# H.net
KiCad netlist of a schematic drawn in EAGLE
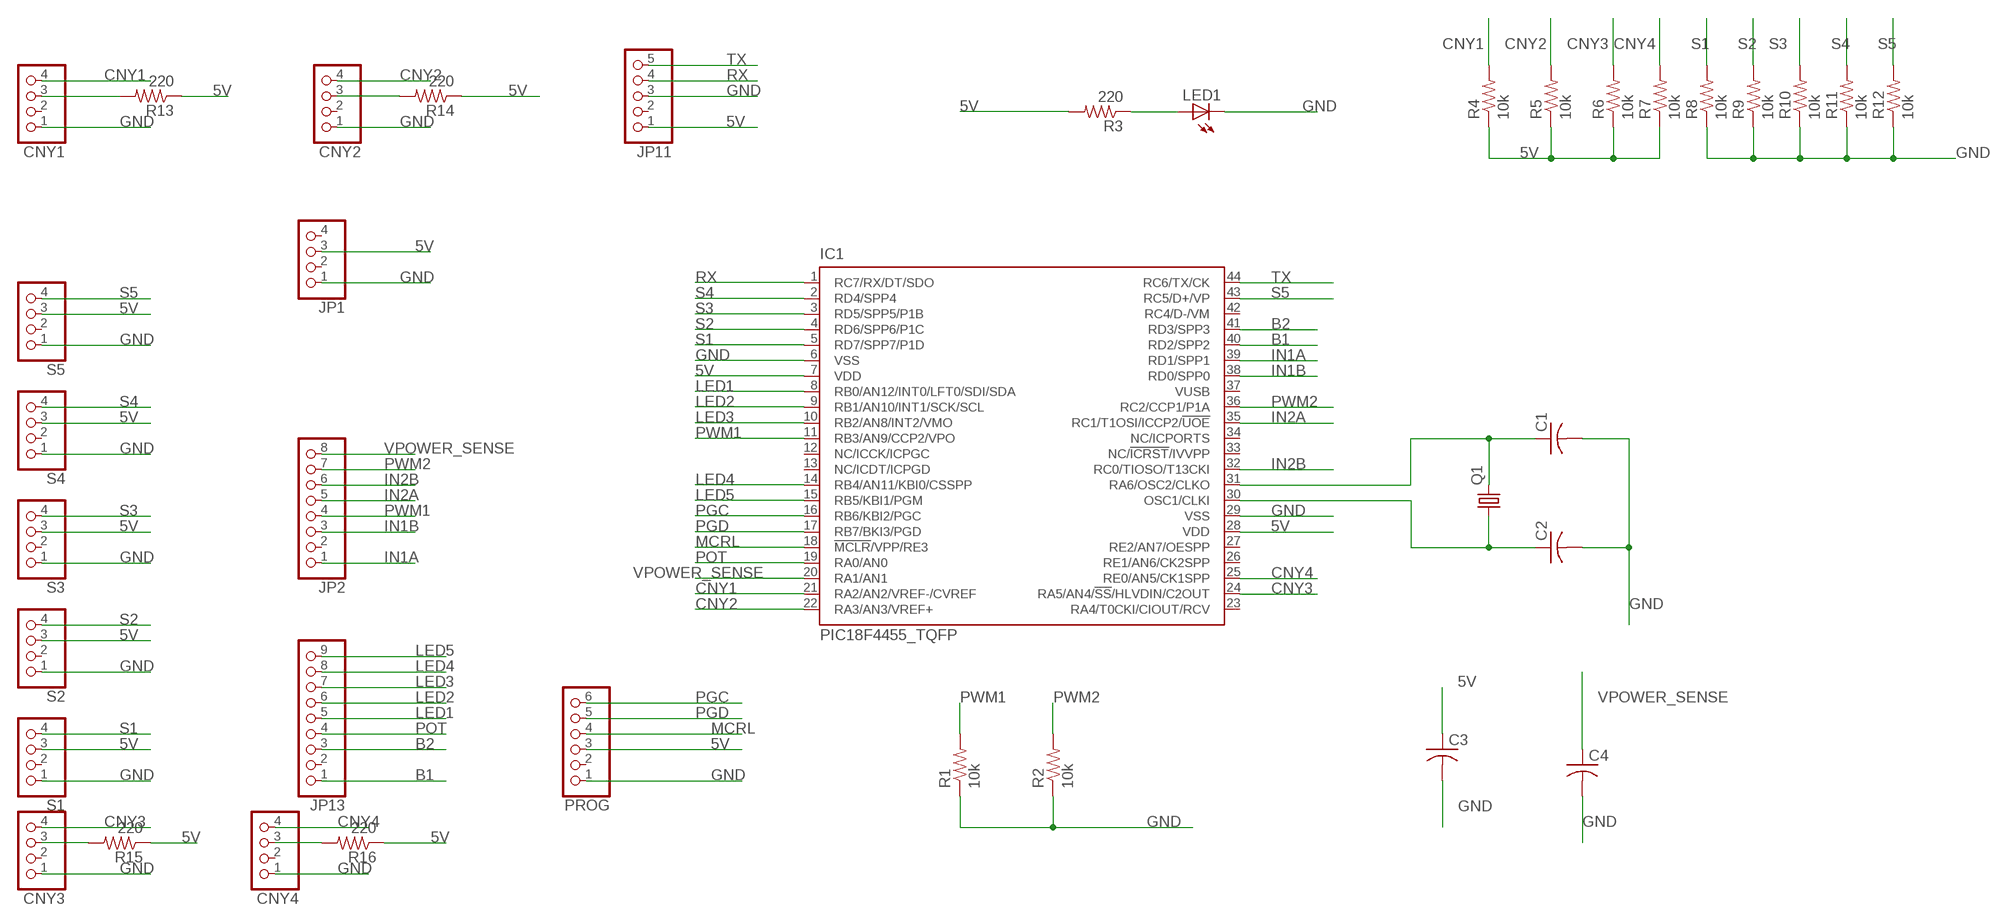
[diagram p0: schematic, sheet 1]

(export (version "E")
  (design (tool "Eeschema 10.0.6"))
  (components
    (comp (ref "C1")
      (value "C-USC0805K")
      (footprint "eagle-import:C0805K")
      (libsource (lib "eagle-import") (part "C-USC0805K"))
    )
    (comp (ref "C2")
      (value "C-USC0805K")
      (footprint "eagle-import:C0805K")
      (libsource (lib "eagle-import") (part "C-USC0805K"))
    )
    (comp (ref "C3")
      (value "C-USC0805K")
      (footprint "eagle-import:C0805K")
      (libsource (lib "eagle-import") (part "C-USC0805K"))
    )
    (comp (ref "C4")
      (value "C-USC0805K")
      (footprint "eagle-import:C0805K")
      (libsource (lib "eagle-import") (part "C-USC0805K"))
    )
    (comp (ref "CNY1")
      (value "PINHD-1X4/90")
      (footprint "eagle-import:1X04_90")
      (libsource (lib "eagle-import") (part "PINHD-1X4/90"))
    )
    (comp (ref "CNY2")
      (value "PINHD-1X4/90")
      (footprint "eagle-import:1X04_90")
      (libsource (lib "eagle-import") (part "PINHD-1X4/90"))
    )
    (comp (ref "CNY3")
      (value "PINHD-1X4/90")
      (footprint "eagle-import:1X04_90")
      (libsource (lib "eagle-import") (part "pinhead-enhanced-3_PINHD-1X4/90"))
    )
    (comp (ref "CNY4")
      (value "PINHD-1X4/90")
      (footprint "eagle-import:1X04_90")
      (libsource (lib "eagle-import") (part "pinhead-enhanced-3_PINHD-1X4/90"))
    )
    (comp (ref "IC1")
      (value "PIC18F4455_TQFP")
      (footprint "eagle-import:TQFP44")
      (fields (field (name "MF") "MICROCHIP") (field (name "MPN") "PIC18F4455-I/PT"))
      (libsource (lib "eagle-import") (part "PIC18F4_TQFP455"))
    )
    (comp (ref "JP1")
      (value "PINHD-1X4/90")
      (footprint "eagle-import:1X04_90")
      (libsource (lib "eagle-import") (part "PINHD-1X4/90"))
    )
    (comp (ref "JP2")
      (value "PINHD-1X8/90")
      (footprint "eagle-import:1X08_90")
      (libsource (lib "eagle-import") (part "PINHD-1X8/90"))
    )
    (comp (ref "JP11")
      (value "PINHD-1X5/90")
      (footprint "eagle-import:1X05_90")
      (libsource (lib "eagle-import") (part "PINHD-1X5/90"))
    )
    (comp (ref "JP13")
      (value "PINHD-1X9/90")
      (footprint "eagle-import:1X09_90")
      (libsource (lib "eagle-import") (part "PINHD-1X9/90"))
    )
    (comp (ref "LED1")
      (value "LEDCHIPLED_1206")
      (footprint "eagle-import:CHIPLED_1206")
      (libsource (lib "eagle-import") (part "LEDCHIPLED_1206"))
    )
    (comp (ref "PROG")
      (value "PINHD-1X6/90")
      (footprint "eagle-import:1X06_90")
      (libsource (lib "eagle-import") (part "PINHD-1X6/90"))
    )
    (comp (ref "Q1")
      (value "CRYSTALHC49S")
      (footprint "eagle-import:HC49_S")
      (libsource (lib "eagle-import") (part "CRYSTALHC49S"))
    )
    (comp (ref "R1")
      (value "10k")
      (footprint "eagle-import:M1206")
      (libsource (lib "eagle-import") (part "R-US_M1206"))
    )
    (comp (ref "R2")
      (value "10k")
      (footprint "eagle-import:M1206")
      (libsource (lib "eagle-import") (part "R-US_M1206"))
    )
    (comp (ref "R3")
      (value "220")
      (footprint "eagle-import:M1206")
      (libsource (lib "eagle-import") (part "R-US_M1206"))
    )
    (comp (ref "R4")
      (value "10k")
      (footprint "eagle-import:M1206")
      (libsource (lib "eagle-import") (part "R-US_M1206"))
    )
    (comp (ref "R5")
      (value "10k")
      (footprint "eagle-import:M1206")
      (libsource (lib "eagle-import") (part "R-US_M1206"))
    )
    (comp (ref "R6")
      (value "10k")
      (footprint "eagle-import:M1206")
      (libsource (lib "eagle-import") (part "R-US_M1206"))
    )
    (comp (ref "R7")
      (value "10k")
      (footprint "eagle-import:M1206")
      (libsource (lib "eagle-import") (part "R-US_M1206"))
    )
    (comp (ref "R8")
      (value "10k")
      (footprint "eagle-import:M1206")
      (libsource (lib "eagle-import") (part "R-US_M1206"))
    )
    (comp (ref "R9")
      (value "10k")
      (footprint "eagle-import:M1206")
      (libsource (lib "eagle-import") (part "R-US_M1206"))
    )
    (comp (ref "R10")
      (value "10k")
      (footprint "eagle-import:M1206")
      (libsource (lib "eagle-import") (part "R-US_M1206"))
    )
    (comp (ref "R11")
      (value "10k")
      (footprint "eagle-import:M1206")
      (libsource (lib "eagle-import") (part "R-US_M1206"))
    )
    (comp (ref "R12")
      (value "10k")
      (footprint "eagle-import:M1206")
      (libsource (lib "eagle-import") (part "R-US_M1206"))
    )
    (comp (ref "R13")
      (value "220")
      (footprint "eagle-import:M1206")
      (libsource (lib "eagle-import") (part "R-US_M1206"))
    )
    (comp (ref "R14")
      (value "220")
      (footprint "eagle-import:M1206")
      (libsource (lib "eagle-import") (part "R-US_M1206"))
    )
    (comp (ref "R15")
      (value "220")
      (footprint "eagle-import:M1206")
      (libsource (lib "eagle-import") (part "R-US_M1206"))
    )
    (comp (ref "R16")
      (value "220")
      (footprint "eagle-import:M1206")
      (libsource (lib "eagle-import") (part "R-US_M1206"))
    )
    (comp (ref "S1")
      (value "PINHD-1X4/90")
      (footprint "eagle-import:1X04_90")
      (libsource (lib "eagle-import") (part "PINHD-1X4/90"))
    )
    (comp (ref "S2")
      (value "PINHD-1X4/90")
      (footprint "eagle-import:1X04_90")
      (libsource (lib "eagle-import") (part "PINHD-1X4/90"))
    )
    (comp (ref "S3")
      (value "PINHD-1X4/90")
      (footprint "eagle-import:1X04_90")
      (libsource (lib "eagle-import") (part "PINHD-1X4/90"))
    )
    (comp (ref "S4")
      (value "PINHD-1X4/90")
      (footprint "eagle-import:1X04_90")
      (libsource (lib "eagle-import") (part "PINHD-1X4/90"))
    )
    (comp (ref "S5")
      (value "PINHD-1X4/90")
      (footprint "eagle-import:1X04_90")
      (libsource (lib "eagle-import") (part "PINHD-1X4/90"))
    )
  )
  (nets
    (net (code "1") (name "/5V") (class "Default")
      (node (ref "C3") (pin "1") (pinfunction "1_1") (pintype "passive"))
      (node (ref "IC1") (pin "28") (pinfunction "VDD_28") (pintype "power_in"))
      (node (ref "IC1") (pin "7") (pinfunction "VDD_7") (pintype "power_in"))
      (node (ref "JP1") (pin "3") (pinfunction "3_3") (pintype "passive"))
      (node (ref "JP11") (pin "1") (pinfunction "1_1") (pintype "passive"))
      (node (ref "PROG") (pin "3") (pinfunction "3_3") (pintype "passive"))
      (node (ref "R13") (pin "1") (pinfunction "1_1") (pintype "passive"))
      (node (ref "R14") (pin "1") (pinfunction "1_1") (pintype "passive"))
      (node (ref "R15") (pin "1") (pinfunction "1_1") (pintype "passive"))
      (node (ref "R16") (pin "1") (pinfunction "1_1") (pintype "passive"))
      (node (ref "R3") (pin "2") (pinfunction "2_2") (pintype "passive"))
      (node (ref "R4") (pin "1") (pinfunction "1_1") (pintype "passive"))
      (node (ref "R5") (pin "1") (pinfunction "1_1") (pintype "passive"))
      (node (ref "R6") (pin "1") (pinfunction "1_1") (pintype "passive"))
      (node (ref "R7") (pin "1") (pinfunction "1_1") (pintype "passive"))
      (node (ref "S1") (pin "3") (pinfunction "3_3") (pintype "passive"))
      (node (ref "S2") (pin "3") (pinfunction "3_3") (pintype "passive"))
      (node (ref "S3") (pin "3") (pinfunction "3_3") (pintype "passive"))
      (node (ref "S4") (pin "3") (pinfunction "3_3") (pintype "passive"))
      (node (ref "S5") (pin "3") (pinfunction "3_3") (pintype "passive"))
    )
    (net (code "2") (name "/B1") (class "Default")
      (node (ref "IC1") (pin "40") (pinfunction "RD2/SPP2_40") (pintype "bidirectional"))
      (node (ref "JP13") (pin "1") (pinfunction "1_1") (pintype "passive"))
    )
    (net (code "3") (name "/B2") (class "Default")
      (node (ref "IC1") (pin "41") (pinfunction "RD3/SPP3_41") (pintype "bidirectional"))
      (node (ref "JP13") (pin "3") (pinfunction "3_3") (pintype "passive"))
    )
    (net (code "4") (name "/CNY1") (class "Default")
      (node (ref "CNY1") (pin "4") (pinfunction "4_4") (pintype "passive"))
      (node (ref "IC1") (pin "21") (pinfunction "RA2/AN2/VREF-/CVREF_21") (pintype "bidirectional"))
      (node (ref "R4") (pin "2") (pinfunction "2_2") (pintype "passive"))
    )
    (net (code "5") (name "/CNY2") (class "Default")
      (node (ref "CNY2") (pin "4") (pinfunction "4_4") (pintype "passive"))
      (node (ref "IC1") (pin "22") (pinfunction "RA3/AN3/VREF+_22") (pintype "bidirectional"))
      (node (ref "R5") (pin "2") (pinfunction "2_2") (pintype "passive"))
    )
    (net (code "6") (name "/CNY3") (class "Default")
      (node (ref "CNY3") (pin "4") (pinfunction "4_4") (pintype "passive"))
      (node (ref "IC1") (pin "24") (pinfunction "RA5/AN4/~{SS}/HLVDIN/C2OUT_24") (pintype "bidirectional"))
      (node (ref "R6") (pin "2") (pinfunction "2_2") (pintype "passive"))
    )
    (net (code "7") (name "/CNY4") (class "Default")
      (node (ref "CNY4") (pin "4") (pinfunction "4_4") (pintype "passive"))
      (node (ref "IC1") (pin "25") (pinfunction "RE0/AN5/CK1SPP_25") (pintype "bidirectional"))
      (node (ref "R7") (pin "2") (pinfunction "2_2") (pintype "passive"))
    )
    (net (code "8") (name "/GND") (class "Default")
      (node (ref "C1") (pin "2") (pinfunction "2_2") (pintype "passive"))
      (node (ref "C2") (pin "2") (pinfunction "2_2") (pintype "passive"))
      (node (ref "C3") (pin "2") (pinfunction "2_2") (pintype "passive"))
      (node (ref "C4") (pin "2") (pinfunction "2_2") (pintype "passive"))
      (node (ref "CNY1") (pin "1") (pinfunction "1_1") (pintype "passive"))
      (node (ref "CNY2") (pin "1") (pinfunction "1_1") (pintype "passive"))
      (node (ref "CNY3") (pin "1") (pinfunction "1_1") (pintype "passive"))
      (node (ref "CNY4") (pin "1") (pinfunction "1_1") (pintype "passive"))
      (node (ref "IC1") (pin "29") (pinfunction "VSS_29") (pintype "power_in"))
      (node (ref "IC1") (pin "6") (pinfunction "VSS_6") (pintype "power_in"))
      (node (ref "JP1") (pin "1") (pinfunction "1_1") (pintype "passive"))
      (node (ref "JP11") (pin "3") (pinfunction "3_3") (pintype "passive"))
      (node (ref "LED1") (pin "C") (pinfunction "C_C") (pintype "passive"))
      (node (ref "PROG") (pin "1") (pinfunction "1_1") (pintype "passive"))
      (node (ref "R1") (pin "1") (pinfunction "1_1") (pintype "passive"))
      (node (ref "R10") (pin "1") (pinfunction "1_1") (pintype "passive"))
      (node (ref "R11") (pin "1") (pinfunction "1_1") (pintype "passive"))
      (node (ref "R12") (pin "1") (pinfunction "1_1") (pintype "passive"))
      (node (ref "R2") (pin "1") (pinfunction "1_1") (pintype "passive"))
      (node (ref "R8") (pin "1") (pinfunction "1_1") (pintype "passive"))
      (node (ref "R9") (pin "1") (pinfunction "1_1") (pintype "passive"))
      (node (ref "S1") (pin "1") (pinfunction "1_1") (pintype "passive"))
      (node (ref "S2") (pin "1") (pinfunction "1_1") (pintype "passive"))
      (node (ref "S3") (pin "1") (pinfunction "1_1") (pintype "passive"))
      (node (ref "S4") (pin "1") (pinfunction "1_1") (pintype "passive"))
      (node (ref "S5") (pin "1") (pinfunction "1_1") (pintype "passive"))
    )
    (net (code "9") (name "/IN1A") (class "Default")
      (node (ref "IC1") (pin "39") (pinfunction "RD1/SPP1_39") (pintype "bidirectional"))
      (node (ref "JP2") (pin "1") (pinfunction "1_1") (pintype "passive"))
    )
    (net (code "10") (name "/IN1B") (class "Default")
      (node (ref "IC1") (pin "38") (pinfunction "RD0/SPP0_38") (pintype "bidirectional"))
      (node (ref "JP2") (pin "3") (pinfunction "3_3") (pintype "passive"))
    )
    (net (code "11") (name "/IN2A") (class "Default")
      (node (ref "IC1") (pin "35") (pinfunction "RC1/T1OSI/ICCP2/~{UOE}_35") (pintype "bidirectional"))
      (node (ref "JP2") (pin "5") (pinfunction "5_5") (pintype "passive"))
    )
    (net (code "12") (name "/IN2B") (class "Default")
      (node (ref "IC1") (pin "32") (pinfunction "RC0/TIOSO/T13CKI_32") (pintype "bidirectional"))
      (node (ref "JP2") (pin "6") (pinfunction "6_6") (pintype "passive"))
    )
    (net (code "13") (name "/LED1") (class "Default")
      (node (ref "IC1") (pin "8") (pinfunction "RB0/AN12/INT0/LFT0/SDI/SDA_8") (pintype "bidirectional"))
      (node (ref "JP13") (pin "5") (pinfunction "5_5") (pintype "passive"))
    )
    (net (code "14") (name "/LED2") (class "Default")
      (node (ref "IC1") (pin "9") (pinfunction "RB1/AN10/INT1/SCK/SCL_9") (pintype "bidirectional"))
      (node (ref "JP13") (pin "6") (pinfunction "6_6") (pintype "passive"))
    )
    (net (code "15") (name "/LED3") (class "Default")
      (node (ref "IC1") (pin "10") (pinfunction "RB2/AN8/INT2/VMO_10") (pintype "bidirectional"))
      (node (ref "JP13") (pin "7") (pinfunction "7_7") (pintype "passive"))
    )
    (net (code "16") (name "/LED4") (class "Default")
      (node (ref "IC1") (pin "14") (pinfunction "RB4/AN11/KBI0/CSSPP_14") (pintype "bidirectional"))
      (node (ref "JP13") (pin "8") (pinfunction "8_8") (pintype "passive"))
    )
    (net (code "17") (name "/LED5") (class "Default")
      (node (ref "IC1") (pin "15") (pinfunction "RB5/KBI1/PGM_15") (pintype "bidirectional"))
      (node (ref "JP13") (pin "9") (pinfunction "9_9") (pintype "passive"))
    )
    (net (code "18") (name "/MCRL") (class "Default")
      (node (ref "IC1") (pin "18") (pinfunction "~{MCLR}/VPP/RE3_18") (pintype "input"))
      (node (ref "PROG") (pin "4") (pinfunction "4_4") (pintype "passive"))
    )
    (net (code "19") (name "/PGC") (class "Default")
      (node (ref "IC1") (pin "16") (pinfunction "RB6/KBI2/PGC_16") (pintype "bidirectional"))
      (node (ref "PROG") (pin "6") (pinfunction "6_6") (pintype "passive"))
    )
    (net (code "20") (name "/PGD") (class "Default")
      (node (ref "IC1") (pin "17") (pinfunction "RB7/BKI3/PGD_17") (pintype "bidirectional"))
      (node (ref "PROG") (pin "5") (pinfunction "5_5") (pintype "passive"))
    )
    (net (code "21") (name "/POT") (class "Default")
      (node (ref "IC1") (pin "19") (pinfunction "RA0/AN0_19") (pintype "bidirectional"))
      (node (ref "JP13") (pin "4") (pinfunction "4_4") (pintype "passive"))
    )
    (net (code "22") (name "/PWM1") (class "Default")
      (node (ref "IC1") (pin "11") (pinfunction "RB3/AN9/CCP2/VPO_11") (pintype "bidirectional"))
      (node (ref "JP2") (pin "4") (pinfunction "4_4") (pintype "passive"))
      (node (ref "R1") (pin "2") (pinfunction "2_2") (pintype "passive"))
    )
    (net (code "23") (name "/PWM2") (class "Default")
      (node (ref "IC1") (pin "36") (pinfunction "RC2/CCP1/P1A_36") (pintype "bidirectional"))
      (node (ref "JP2") (pin "7") (pinfunction "7_7") (pintype "passive"))
      (node (ref "R2") (pin "2") (pinfunction "2_2") (pintype "passive"))
    )
    (net (code "24") (name "/RX") (class "Default")
      (node (ref "IC1") (pin "1") (pinfunction "RC7/RX/DT/SDO_1") (pintype "bidirectional"))
      (node (ref "JP11") (pin "4") (pinfunction "4_4") (pintype "passive"))
    )
    (net (code "25") (name "/S1") (class "Default")
      (node (ref "IC1") (pin "5") (pinfunction "RD7/SPP7/P1D_5") (pintype "bidirectional"))
      (node (ref "R8") (pin "2") (pinfunction "2_2") (pintype "passive"))
      (node (ref "S1") (pin "4") (pinfunction "4_4") (pintype "passive"))
    )
    (net (code "26") (name "/S2") (class "Default")
      (node (ref "IC1") (pin "4") (pinfunction "RD6/SPP6/P1C_4") (pintype "bidirectional"))
      (node (ref "R9") (pin "2") (pinfunction "2_2") (pintype "passive"))
      (node (ref "S2") (pin "4") (pinfunction "4_4") (pintype "passive"))
    )
    (net (code "27") (name "/S3") (class "Default")
      (node (ref "IC1") (pin "3") (pinfunction "RD5/SPP5/P1B_3") (pintype "bidirectional"))
      (node (ref "R10") (pin "2") (pinfunction "2_2") (pintype "passive"))
      (node (ref "S3") (pin "4") (pinfunction "4_4") (pintype "passive"))
    )
    (net (code "28") (name "/S4") (class "Default")
      (node (ref "IC1") (pin "2") (pinfunction "RD4/SPP4_2") (pintype "bidirectional"))
      (node (ref "R11") (pin "2") (pinfunction "2_2") (pintype "passive"))
      (node (ref "S4") (pin "4") (pinfunction "4_4") (pintype "passive"))
    )
    (net (code "29") (name "/S5") (class "Default")
      (node (ref "IC1") (pin "43") (pinfunction "RC5/D+/VP_43") (pintype "bidirectional"))
      (node (ref "R12") (pin "2") (pinfunction "2_2") (pintype "passive"))
      (node (ref "S5") (pin "4") (pinfunction "4_4") (pintype "passive"))
    )
    (net (code "30") (name "/TX") (class "Default")
      (node (ref "IC1") (pin "44") (pinfunction "RC6/TX/CK_44") (pintype "bidirectional"))
      (node (ref "JP11") (pin "5") (pinfunction "5_5") (pintype "passive"))
    )
    (net (code "31") (name "/VPOWER_SENSE") (class "Default")
      (node (ref "C4") (pin "1") (pinfunction "1_1") (pintype "passive"))
      (node (ref "IC1") (pin "20") (pinfunction "RA1/AN1_20") (pintype "bidirectional"))
      (node (ref "JP2") (pin "8") (pinfunction "8_8") (pintype "passive"))
    )
    (net (code "32") (name "Net-(CNY1-Pad3)") (class "Default")
      (node (ref "CNY1") (pin "3") (pinfunction "3_3") (pintype "passive"))
      (node (ref "R13") (pin "2") (pinfunction "2_2") (pintype "passive"))
    )
    (net (code "33") (name "Net-(CNY2-Pad3)") (class "Default")
      (node (ref "CNY2") (pin "3") (pinfunction "3_3") (pintype "passive"))
      (node (ref "R14") (pin "2") (pinfunction "2_2") (pintype "passive"))
    )
    (net (code "34") (name "Net-(CNY3-Pad3)") (class "Default")
      (node (ref "CNY3") (pin "3") (pinfunction "3_3") (pintype "passive"))
      (node (ref "R15") (pin "2") (pinfunction "2_2") (pintype "passive"))
    )
    (net (code "35") (name "Net-(CNY4-Pad3)") (class "Default")
      (node (ref "CNY4") (pin "3") (pinfunction "3_3") (pintype "passive"))
      (node (ref "R16") (pin "2") (pinfunction "2_2") (pintype "passive"))
    )
    (net (code "36") (name "Net-(IC1-OSC1{slash}CLKI)") (class "Default")
      (node (ref "C2") (pin "1") (pinfunction "1_1") (pintype "passive"))
      (node (ref "IC1") (pin "30") (pinfunction "OSC1/CLKI_30") (pintype "input"))
      (node (ref "Q1") (pin "1") (pinfunction "1_1") (pintype "passive"))
    )
    (net (code "37") (name "Net-(IC1-RA6{slash}OSC2{slash}CLKO)") (class "Default")
      (node (ref "C1") (pin "1") (pinfunction "1_1") (pintype "passive"))
      (node (ref "IC1") (pin "31") (pinfunction "RA6/OSC2/CLKO_31") (pintype "output"))
      (node (ref "Q1") (pin "2") (pinfunction "2_2") (pintype "passive"))
    )
    (net (code "38") (name "Net-(LED1-PadA)") (class "Default")
      (node (ref "LED1") (pin "A") (pinfunction "A_A") (pintype "passive"))
      (node (ref "R3") (pin "1") (pinfunction "1_1") (pintype "passive"))
    )
    (net (code "39") (name "unconnected-(CNY1-Pad2)") (class "Default")
      (node (ref "CNY1") (pin "2") (pinfunction "2_2") (pintype "passive"))
    )
    (net (code "40") (name "unconnected-(CNY2-Pad2)") (class "Default")
      (node (ref "CNY2") (pin "2") (pinfunction "2_2") (pintype "passive"))
    )
    (net (code "41") (name "unconnected-(CNY3-Pad2)") (class "Default")
      (node (ref "CNY3") (pin "2") (pinfunction "2_2") (pintype "passive"))
    )
    (net (code "42") (name "unconnected-(CNY4-Pad2)") (class "Default")
      (node (ref "CNY4") (pin "2") (pinfunction "2_2") (pintype "passive"))
    )
    (net (code "43") (name "unconnected-(IC1-NC{slash}ICCK{slash}ICPGC-Pad12)") (class "Default")
      (node (ref "IC1") (pin "12") (pinfunction "NC/ICCK/ICPGC_12") (pintype "bidirectional"))
    )
    (net (code "44") (name "unconnected-(IC1-NC{slash}ICDT{slash}ICPGD-Pad13)") (class "Default")
      (node (ref "IC1") (pin "13") (pinfunction "NC/ICDT/ICPGD_13") (pintype "bidirectional"))
    )
    (net (code "45") (name "unconnected-(IC1-NC{slash}ICPORTS-Pad34)") (class "Default")
      (node (ref "IC1") (pin "34") (pinfunction "NC/ICPORTS_34") (pintype "input"))
    )
    (net (code "46") (name "unconnected-(IC1-NC{slash}~{ICRST}{slash}IVVPP-Pad33)") (class "Default")
      (node (ref "IC1") (pin "33") (pinfunction "NC/~{ICRST}/IVVPP_33") (pintype "input"))
    )
    (net (code "47") (name "unconnected-(IC1-RA4{slash}T0CKI{slash}CIOUT{slash}RCV-Pad23)") (class "Default")
      (node (ref "IC1") (pin "23") (pinfunction "RA4/T0CKI/CIOUT/RCV_23") (pintype "bidirectional"))
    )
    (net (code "48") (name "unconnected-(IC1-RC4{slash}D-{slash}VM-Pad42)") (class "Default")
      (node (ref "IC1") (pin "42") (pinfunction "RC4/D-/VM_42") (pintype "bidirectional"))
    )
    (net (code "49") (name "unconnected-(IC1-RE1{slash}AN6{slash}CK2SPP-Pad26)") (class "Default")
      (node (ref "IC1") (pin "26") (pinfunction "RE1/AN6/CK2SPP_26") (pintype "bidirectional"))
    )
    (net (code "50") (name "unconnected-(IC1-RE2{slash}AN7{slash}OESPP-Pad27)") (class "Default")
      (node (ref "IC1") (pin "27") (pinfunction "RE2/AN7/OESPP_27") (pintype "bidirectional"))
    )
    (net (code "51") (name "unconnected-(IC1-VUSB-Pad37)") (class "Default")
      (node (ref "IC1") (pin "37") (pinfunction "VUSB_37") (pintype "bidirectional"))
    )
    (net (code "52") (name "unconnected-(JP1-Pad2)") (class "Default")
      (node (ref "JP1") (pin "2") (pinfunction "2_2") (pintype "passive"))
    )
    (net (code "53") (name "unconnected-(JP1-Pad4)") (class "Default")
      (node (ref "JP1") (pin "4") (pinfunction "4_4") (pintype "passive"))
    )
    (net (code "54") (name "unconnected-(JP2-Pad2)") (class "Default")
      (node (ref "JP2") (pin "2") (pinfunction "2_2") (pintype "passive"))
    )
    (net (code "55") (name "unconnected-(JP11-Pad2)") (class "Default")
      (node (ref "JP11") (pin "2") (pinfunction "2_2") (pintype "passive"))
    )
    (net (code "56") (name "unconnected-(JP13-Pad2)") (class "Default")
      (node (ref "JP13") (pin "2") (pinfunction "2_2") (pintype "passive"))
    )
    (net (code "57") (name "unconnected-(PROG-Pad2)") (class "Default")
      (node (ref "PROG") (pin "2") (pinfunction "2_2") (pintype "passive"))
    )
    (net (code "58") (name "unconnected-(S1-Pad2)") (class "Default")
      (node (ref "S1") (pin "2") (pinfunction "2_2") (pintype "passive"))
    )
    (net (code "59") (name "unconnected-(S2-Pad2)") (class "Default")
      (node (ref "S2") (pin "2") (pinfunction "2_2") (pintype "passive"))
    )
    (net (code "60") (name "unconnected-(S3-Pad2)") (class "Default")
      (node (ref "S3") (pin "2") (pinfunction "2_2") (pintype "passive"))
    )
    (net (code "61") (name "unconnected-(S4-Pad2)") (class "Default")
      (node (ref "S4") (pin "2") (pinfunction "2_2") (pintype "passive"))
    )
    (net (code "62") (name "unconnected-(S5-Pad2)") (class "Default")
      (node (ref "S5") (pin "2") (pinfunction "2_2") (pintype "passive"))
    )
  )
)
